# VM-MCU_v4_6.net
KiCad netlist of a schematic drawn in EAGLE
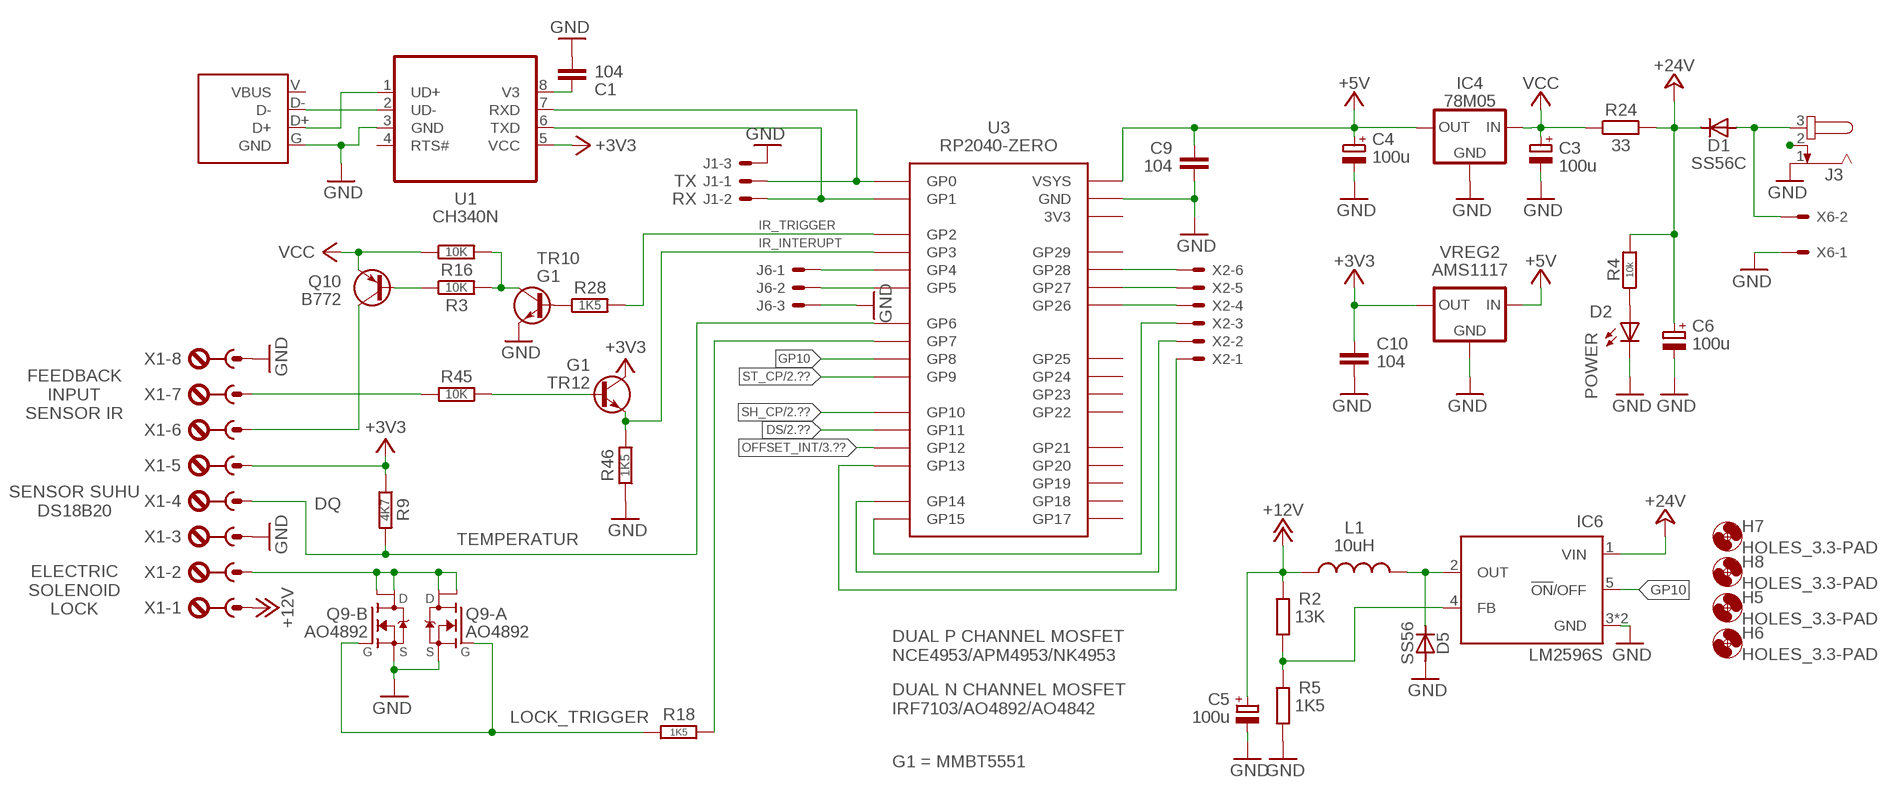
[diagram p0: schematic, sheet 1]
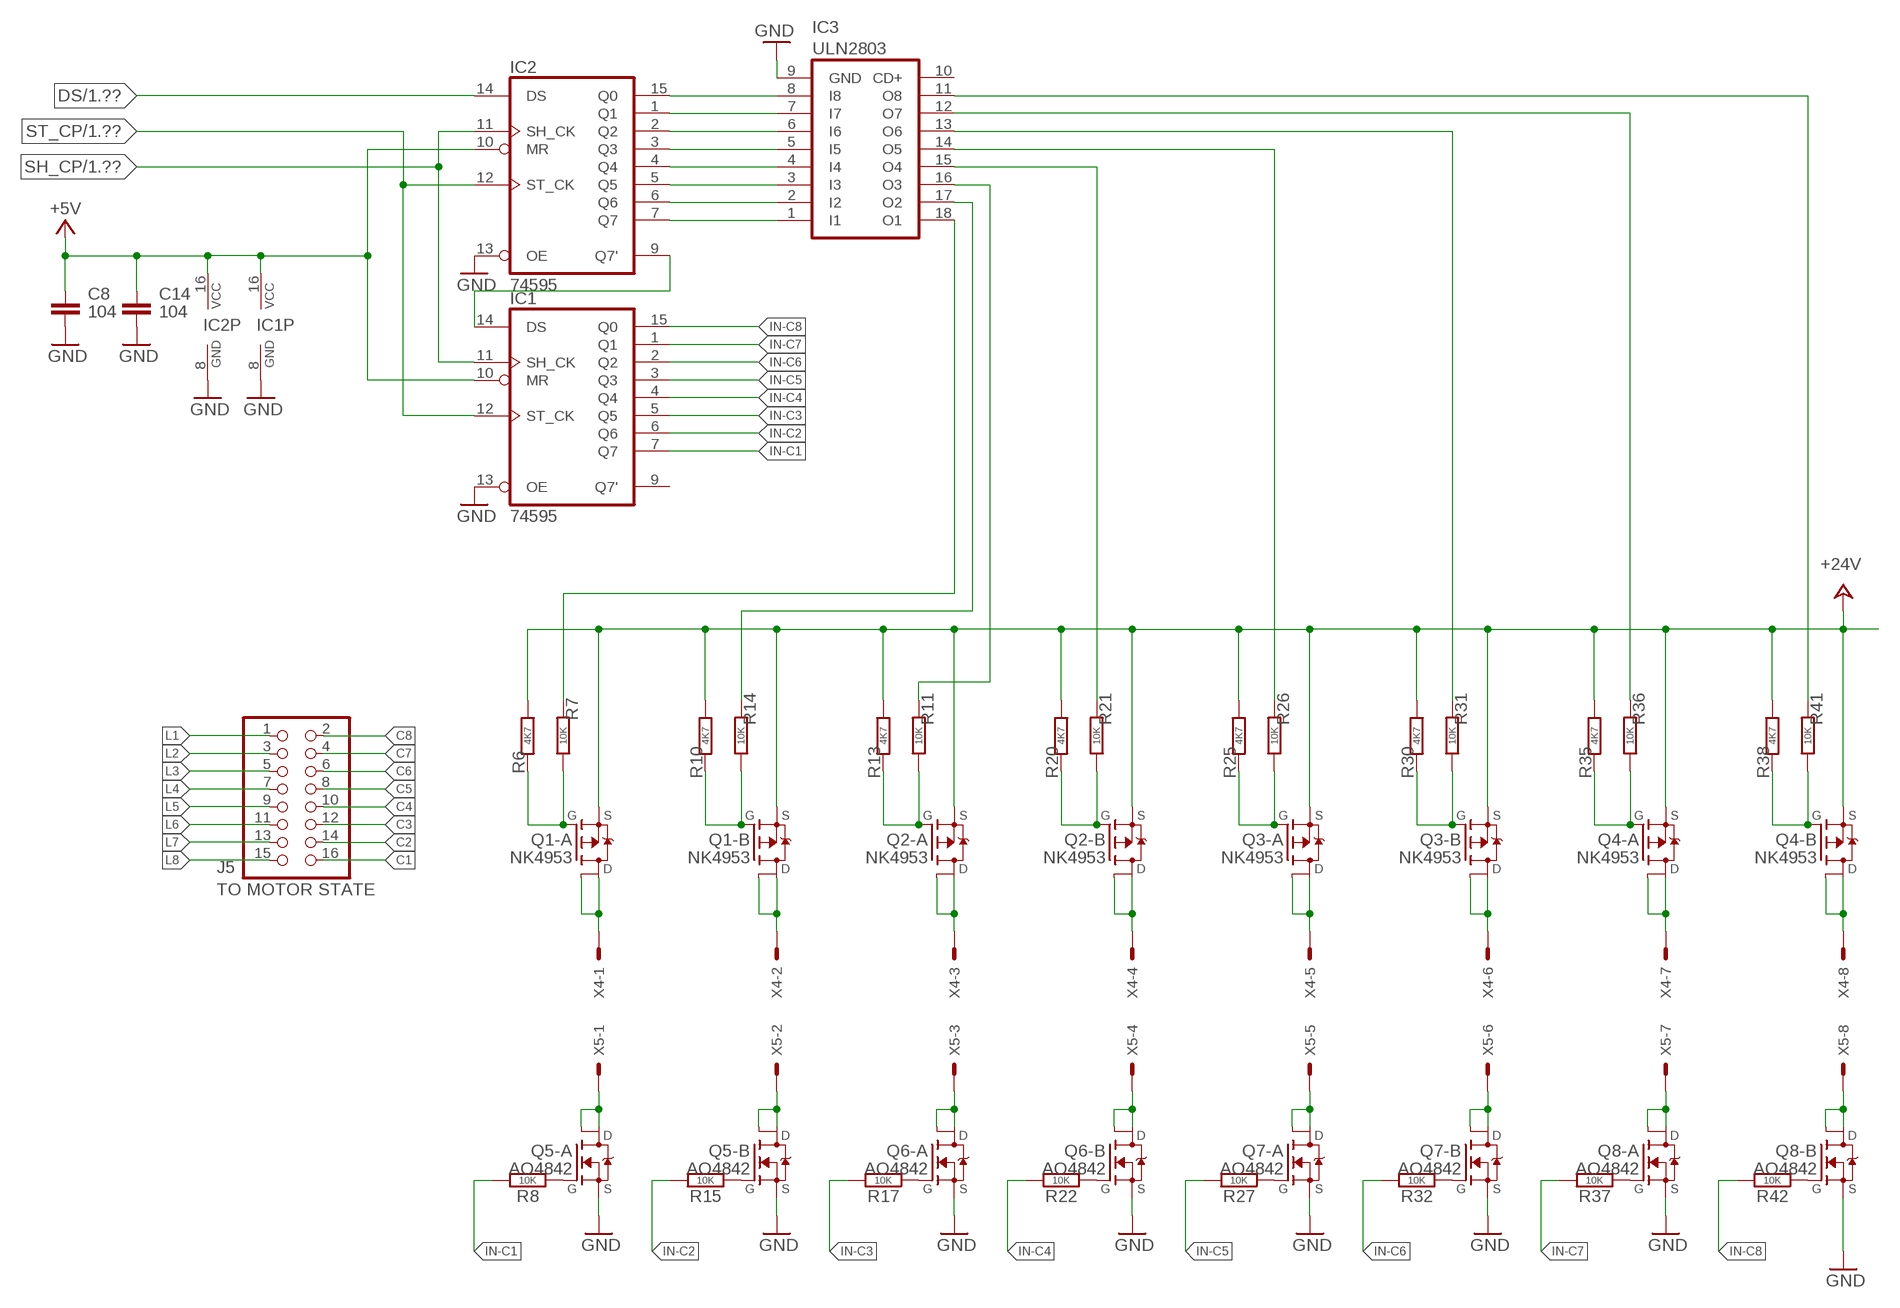
[diagram p1: schematic, sheet 2]
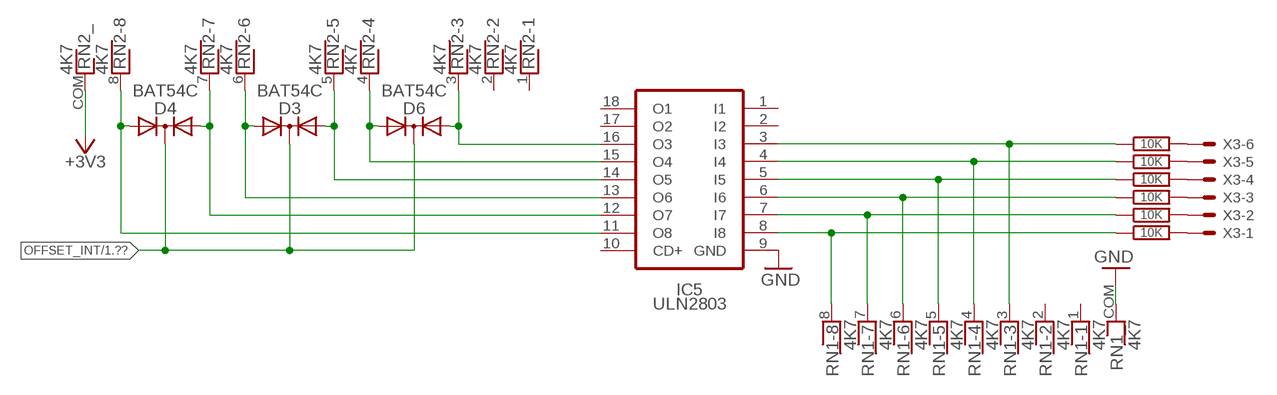
[diagram p2: schematic, sheet 3]

(export (version "E")
  (design (tool "Eeschema 10.0.6"))
  (components
    (comp (ref "C8")
      (value "104")
      (footprint "eagle-import:C1206")
      (libsource (lib "eagle-import") (part "CAP_SMD-C1206"))
    )
    (comp (ref "C14")
      (value "104")
      (footprint "eagle-import:C1206")
      (libsource (lib "eagle-import") (part "CAP_SMD-C1206"))
    )
    (comp (ref "IC1")
      (value "74595")
      (footprint "eagle-import:SO16")
      (libsource (lib "eagle-import") (part "74595"))
    )
    (comp (ref "IC2")
      (value "74595")
      (footprint "eagle-import:SO16")
      (libsource (lib "eagle-import") (part "74595"))
    )
    (comp (ref "IC3")
      (value "ULN2803")
      (footprint "eagle-import:SO18W")
      (libsource (lib "eagle-import") (part "ULN2805ASO18"))
    )
    (comp (ref "J5")
      (value "TO MOTOR STATE")
      (footprint "eagle-import:PINHEAD-SMT_2X08")
      (libsource (lib "eagle-import") (part "PINHEAD_2X8SMT"))
    )
    (comp (ref "Q1")
      (value "NK4953")
      (footprint "eagle-import:SO-8")
      (libsource (lib "eagle-import") (part "DUALFET-P_P+PNCE4953"))
    )
    (comp (ref "Q2")
      (value "NK4953")
      (footprint "eagle-import:SO-8")
      (libsource (lib "eagle-import") (part "DUALFET-P_P+PNCE4953"))
    )
    (comp (ref "Q3")
      (value "NK4953")
      (footprint "eagle-import:SO-8")
      (libsource (lib "eagle-import") (part "DUALFET-P_P+PNCE4953"))
    )
    (comp (ref "Q4")
      (value "NK4953")
      (footprint "eagle-import:SO-8")
      (libsource (lib "eagle-import") (part "DUALFET-P_P+PNCE4953"))
    )
    (comp (ref "Q5")
      (value "AO4842")
      (footprint "eagle-import:SO-8")
      (libsource (lib "eagle-import") (part "DUALFET-N_N+NAO4892"))
    )
    (comp (ref "Q6")
      (value "AO4842")
      (footprint "eagle-import:SO-8")
      (libsource (lib "eagle-import") (part "DUALFET-N_N+NAO4892"))
    )
    (comp (ref "Q7")
      (value "AO4842")
      (footprint "eagle-import:SO-8")
      (libsource (lib "eagle-import") (part "DUALFET-N_N+NAO4892"))
    )
    (comp (ref "Q8")
      (value "AO4842")
      (footprint "eagle-import:SO-8")
      (libsource (lib "eagle-import") (part "DUALFET-N_N+NAO4892"))
    )
    (comp (ref "R6")
      (value "4K7")
      (footprint "eagle-import:R1206")
      (libsource (lib "eagle-import") (part "RESISTOR_1206"))
    )
    (comp (ref "R7")
      (value "10K")
      (footprint "eagle-import:R1206")
      (libsource (lib "eagle-import") (part "RESISTOR_1206"))
    )
    (comp (ref "R8")
      (value "10K")
      (footprint "eagle-import:R1206")
      (libsource (lib "eagle-import") (part "RESISTOR_1206"))
    )
    (comp (ref "R10")
      (value "4K7")
      (footprint "eagle-import:R1206")
      (libsource (lib "eagle-import") (part "RESISTOR_1206"))
    )
    (comp (ref "R11")
      (value "10K")
      (footprint "eagle-import:R1206")
      (libsource (lib "eagle-import") (part "RESISTOR_1206"))
    )
    (comp (ref "R13")
      (value "4K7")
      (footprint "eagle-import:R1206")
      (libsource (lib "eagle-import") (part "RESISTOR_1206"))
    )
    (comp (ref "R14")
      (value "10K")
      (footprint "eagle-import:R1206")
      (libsource (lib "eagle-import") (part "RESISTOR_1206"))
    )
    (comp (ref "R15")
      (value "10K")
      (footprint "eagle-import:R1206")
      (libsource (lib "eagle-import") (part "RESISTOR_1206"))
    )
    (comp (ref "R17")
      (value "10K")
      (footprint "eagle-import:R1206")
      (libsource (lib "eagle-import") (part "RESISTOR_1206"))
    )
    (comp (ref "R20")
      (value "4K7")
      (footprint "eagle-import:R1206")
      (libsource (lib "eagle-import") (part "RESISTOR_1206"))
    )
    (comp (ref "R21")
      (value "10K")
      (footprint "eagle-import:R1206")
      (libsource (lib "eagle-import") (part "RESISTOR_1206"))
    )
    (comp (ref "R22")
      (value "10K")
      (footprint "eagle-import:R1206")
      (libsource (lib "eagle-import") (part "RESISTOR_1206"))
    )
    (comp (ref "R25")
      (value "4K7")
      (footprint "eagle-import:R1206")
      (libsource (lib "eagle-import") (part "RESISTOR_1206"))
    )
    (comp (ref "R26")
      (value "10K")
      (footprint "eagle-import:R1206")
      (libsource (lib "eagle-import") (part "RESISTOR_1206"))
    )
    (comp (ref "R27")
      (value "10K")
      (footprint "eagle-import:R1206")
      (libsource (lib "eagle-import") (part "RESISTOR_1206"))
    )
    (comp (ref "R30")
      (value "4K7")
      (footprint "eagle-import:R1206")
      (libsource (lib "eagle-import") (part "RESISTOR_1206"))
    )
    (comp (ref "R31")
      (value "10K")
      (footprint "eagle-import:R1206")
      (libsource (lib "eagle-import") (part "RESISTOR_1206"))
    )
    (comp (ref "R32")
      (value "10K")
      (footprint "eagle-import:R1206")
      (libsource (lib "eagle-import") (part "RESISTOR_1206"))
    )
    (comp (ref "R35")
      (value "4K7")
      (footprint "eagle-import:R1206")
      (libsource (lib "eagle-import") (part "RESISTOR_1206"))
    )
    (comp (ref "R36")
      (value "10K")
      (footprint "eagle-import:R1206")
      (libsource (lib "eagle-import") (part "RESISTOR_1206"))
    )
    (comp (ref "R37")
      (value "10K")
      (footprint "eagle-import:R1206")
      (libsource (lib "eagle-import") (part "RESISTOR_1206"))
    )
    (comp (ref "R38")
      (value "4K7")
      (footprint "eagle-import:R1206")
      (libsource (lib "eagle-import") (part "RESISTOR_1206"))
    )
    (comp (ref "R41")
      (value "10K")
      (footprint "eagle-import:R1206")
      (libsource (lib "eagle-import") (part "RESISTOR_1206"))
    )
    (comp (ref "R42")
      (value "10K")
      (footprint "eagle-import:R1206")
      (libsource (lib "eagle-import") (part "RESISTOR_1206"))
    )
    (comp (ref "X4")
      (value "SOKET-8P_MOLEX-3.96")
      (footprint "eagle-import:8P-MOLEX")
      (fields (field (name "MF") "MOLEX"))
      (libsource (lib "eagle-import") (part "SOKET-8P_MOLEX-3.96"))
    )
    (comp (ref "X5")
      (value "SOKET-8P_MOLEX-3.96")
      (footprint "eagle-import:8P-MOLEX")
      (fields (field (name "MF") "MOLEX"))
      (libsource (lib "eagle-import") (part "SOKET-8P_MOLEX-3.96"))
    )
    (comp (ref "C1")
      (value "104")
      (footprint "eagle-import:C1206")
      (libsource (lib "eagle-import") (part "CAP_SMD-C1206"))
    )
    (comp (ref "C3")
      (value "100u")
      (footprint "eagle-import:UD-6,3X7,7_NICHICON")
      (libsource (lib "eagle-import") (part "ELCO_UD-6,3X7,7"))
    )
    (comp (ref "C4")
      (value "100u")
      (footprint "eagle-import:UD-6,3X7,7_NICHICON")
      (libsource (lib "eagle-import") (part "ELCO_UD-6,3X7,7"))
    )
    (comp (ref "C5")
      (value "100u")
      (footprint "eagle-import:UD-6,3X7,7_NICHICON")
      (libsource (lib "eagle-import") (part "ELCO_UD-6,3X7,7"))
    )
    (comp (ref "C6")
      (value "100u")
      (footprint "eagle-import:UD-6,3X7,7_NICHICON")
      (libsource (lib "eagle-import") (part "ELCO_UD-6,3X7,7"))
    )
    (comp (ref "C9")
      (value "104")
      (footprint "eagle-import:C1206")
      (libsource (lib "eagle-import") (part "CAP_SMD-C1206"))
    )
    (comp (ref "C10")
      (value "104")
      (footprint "eagle-import:C1206")
      (libsource (lib "eagle-import") (part "CAP_SMD-C1206"))
    )
    (comp (ref "D1")
      (value "SS56C")
      (footprint "eagle-import:DO214AB")
      (libsource (lib "eagle-import") (part "DIODE_DO214AB-SMC"))
    )
    (comp (ref "D2")
      (value "POWER")
      (footprint "eagle-import:LED2835")
      (libsource (lib "eagle-import") (part "LED2835"))
    )
    (comp (ref "D5")
      (value "SS56")
      (footprint "eagle-import:DO214AC")
      (libsource (lib "eagle-import") (part "DIODE_DO214AC"))
    )
    (comp (ref "H5")
      (value "HOLES_3.3-PAD")
      (footprint "eagle-import:3,3-PAD")
      (libsource (lib "eagle-import") (part "HOLES_3.3-PAD"))
    )
    (comp (ref "H6")
      (value "HOLES_3.3-PAD")
      (footprint "eagle-import:3,3-PAD")
      (libsource (lib "eagle-import") (part "HOLES_3.3-PAD"))
    )
    (comp (ref "H7")
      (value "HOLES_3.3-PAD")
      (footprint "eagle-import:3,3-PAD")
      (libsource (lib "eagle-import") (part "HOLES_3.3-PAD"))
    )
    (comp (ref "H8")
      (value "HOLES_3.3-PAD")
      (footprint "eagle-import:3,3-PAD")
      (libsource (lib "eagle-import") (part "HOLES_3.3-PAD"))
    )
    (comp (ref "IC4")
      (value "78M05")
      (footprint "eagle-import:TO252")
      (libsource (lib "eagle-import") (part "78XXX_TO252"))
    )
    (comp (ref "IC6")
      (value "LM2596S")
      (footprint "eagle-import:TO263-5")
      (fields (field (name "MF") "NATIONAL SEMICONDUCTOR") (field (name "MPN") "LM2596S-ADJ/NOPB"))
      (libsource (lib "eagle-import") (part "LM2596S"))
    )
    (comp (ref "J1")
      (value "SOKET-3P_JST-XH-2.54")
      (footprint "eagle-import:3P-JST-XH")
      (libsource (lib "eagle-import") (part "SOKET-3P_JST-XH-2.54"))
    )
    (comp (ref "J3")
      (value "JACK-DC_5.5X2.1MM")
      (footprint "eagle-import:DC-5.5X2.1")
      (libsource (lib "eagle-import") (part "JACK-DC_5.5X2.1MM"))
    )
    (comp (ref "J6")
      (value "SOKET-3P_JST-XH-2.54")
      (footprint "eagle-import:3P-JST-XH")
      (libsource (lib "eagle-import") (part "SOKET-3P_JST-XH-2.54"))
    )
    (comp (ref "L1")
      (value "10uH")
      (footprint "eagle-import:CDRH127_LD")
      (libsource (lib "eagle-import") (part "INDUKTORSMD"))
    )
    (comp (ref "Q9")
      (value "AO4892")
      (footprint "eagle-import:SO-8")
      (libsource (lib "eagle-import") (part "DUALFET-N_N+NAO4892"))
    )
    (comp (ref "Q10")
      (value "B772")
      (footprint "eagle-import:SOT89-BCE")
      (libsource (lib "eagle-import") (part "BJT-PNP_SOT89"))
    )
    (comp (ref "R2")
      (value "13K")
      (footprint "eagle-import:R1206")
      (libsource (lib "eagle-import") (part "VM-MCU_RESISTOR_1206"))
    )
    (comp (ref "R3")
      (value "10K")
      (footprint "eagle-import:R1206")
      (libsource (lib "eagle-import") (part "VM-MCU_RESISTOR_1206"))
    )
    (comp (ref "R4")
      (value "10k")
      (footprint "eagle-import:R1206")
      (libsource (lib "eagle-import") (part "RESISTOR_1206"))
    )
    (comp (ref "R5")
      (value "1K5")
      (footprint "eagle-import:R1206")
      (libsource (lib "eagle-import") (part "VM-MCU_RESISTOR_1206"))
    )
    (comp (ref "R9")
      (value "4K7")
      (footprint "eagle-import:R1206")
      (libsource (lib "eagle-import") (part "VM-MCU_RESISTOR_1206"))
    )
    (comp (ref "R16")
      (value "10K")
      (footprint "eagle-import:R1206")
      (libsource (lib "eagle-import") (part "VM-MCU_RESISTOR_1206"))
    )
    (comp (ref "R18")
      (value "1K5")
      (footprint "eagle-import:R1206")
      (libsource (lib "eagle-import") (part "VM-MCU_RESISTOR_1206"))
    )
    (comp (ref "R24")
      (value "33")
      (footprint "eagle-import:2W-15")
      (libsource (lib "eagle-import") (part "RESISTOR_0615/15"))
    )
    (comp (ref "R28")
      (value "1K5")
      (footprint "eagle-import:R1206")
      (libsource (lib "eagle-import") (part "VM-MCU_RESISTOR_1206"))
    )
    (comp (ref "R45")
      (value "10K")
      (footprint "eagle-import:R1206")
      (libsource (lib "eagle-import") (part "RESISTOR_1206"))
    )
    (comp (ref "R46")
      (value "1K5")
      (footprint "eagle-import:R1206")
      (libsource (lib "eagle-import") (part "VM-MCU_RESISTOR_1206"))
    )
    (comp (ref "TR10")
      (value "G1")
      (footprint "eagle-import:SOT23-BEC")
      (libsource (lib "eagle-import") (part "BJT-NPN_SOT23-BEC"))
    )
    (comp (ref "TR12")
      (value "G1")
      (footprint "eagle-import:SOT23-BEC")
      (libsource (lib "eagle-import") (part "BJT-NPN_SOT23-BEC"))
    )
    (comp (ref "U$3")
      (value "USB-C_BREAKOUT_")
      (footprint "eagle-import:USB-C_4P")
      (libsource (lib "eagle-import") (part "USB-C_BREAKOUT_"))
    )
    (comp (ref "U1")
      (value "CH340N")
      (footprint "eagle-import:SO-8")
      (libsource (lib "eagle-import") (part "CH340N"))
    )
    (comp (ref "U3")
      (value "RP2040-ZERO")
      (footprint "eagle-import:PICO-ZERO")
      (libsource (lib "eagle-import") (part "RASPBERRY-PICO-ZERO_"))
    )
    (comp (ref "VREG2")
      (value "AMS1117")
      (footprint "eagle-import:SOT223")
      (libsource (lib "eagle-import") (part "78XXX_SOT223"))
    )
    (comp (ref "X1")
      (value "TBLOCK-8P_KF2EDG-3.81")
      (footprint "eagle-import:KF2EDG-3.81_8P")
      (libsource (lib "eagle-import") (part "TBLOCK-8P_KF2EDG-3.81"))
    )
    (comp (ref "X2")
      (value "SOKET-6P_JST-XH-2.54")
      (footprint "eagle-import:6P-JST-XH")
      (libsource (lib "eagle-import") (part "SOKET-6P_JST-XH-2.54"))
    )
    (comp (ref "X6")
      (value "SOKET-2P_MOLEX-3.96")
      (footprint "eagle-import:2P-MOLEX")
      (fields (field (name "MF") "MOLEX"))
      (libsource (lib "eagle-import") (part "SOKET-2P_MOLEX-3.96"))
    )
    (comp (ref "D3")
      (value "BAT54C")
      (footprint "eagle-import:SOT23-BCE")
      (libsource (lib "eagle-import") (part "DIODE-3PIN_COMMON-CATHODE"))
    )
    (comp (ref "D4")
      (value "BAT54C")
      (footprint "eagle-import:SOT23-BCE")
      (libsource (lib "eagle-import") (part "DIODE-3PIN_COMMON-CATHODE"))
    )
    (comp (ref "D6")
      (value "BAT54C")
      (footprint "eagle-import:SOT23-BCE")
      (libsource (lib "eagle-import") (part "DIODE-3PIN_COMMON-CATHODE"))
    )
    (comp (ref "IC5")
      (value "ULN2803")
      (footprint "eagle-import:SO18W")
      (libsource (lib "eagle-import") (part "ULN2805ASO18"))
    )
    (comp (ref "R39")
      (value "10K")
      (footprint "eagle-import:R1206")
      (libsource (lib "eagle-import") (part "VM-MCU_RESISTOR_1206"))
    )
    (comp (ref "R43")
      (value "10K")
      (footprint "eagle-import:R1206")
      (libsource (lib "eagle-import") (part "VM-MCU_RESISTOR_1206"))
    )
    (comp (ref "R44")
      (value "10K")
      (footprint "eagle-import:R1206")
      (libsource (lib "eagle-import") (part "VM-MCU_RESISTOR_1206"))
    )
    (comp (ref "R47")
      (value "10K")
      (footprint "eagle-import:R1206")
      (libsource (lib "eagle-import") (part "VM-MCU_RESISTOR_1206"))
    )
    (comp (ref "R48")
      (value "10K")
      (footprint "eagle-import:R1206")
      (libsource (lib "eagle-import") (part "VM-MCU_RESISTOR_1206"))
    )
    (comp (ref "R49")
      (value "10K")
      (footprint "eagle-import:R1206")
      (libsource (lib "eagle-import") (part "VM-MCU_RESISTOR_1206"))
    )
    (comp (ref "RN1")
      (value "4K7")
      (footprint "eagle-import:RN-9")
      (libsource (lib "eagle-import") (part "RESISTOR-PACK-X8_"))
    )
    (comp (ref "RN2")
      (value "4K7")
      (footprint "eagle-import:RN-9")
      (libsource (lib "eagle-import") (part "RESISTOR-PACK-X8_"))
    )
    (comp (ref "X3")
      (value "SOKET-6P_MOLEX-3.96")
      (footprint "eagle-import:6P-MOLEX")
      (fields (field (name "MF") "MOLEX"))
      (libsource (lib "eagle-import") (part "SOKET-6P_MOLEX-3.96"))
    )
  )
  (nets
    (net (code "1") (name "+3V3") (class "Default")
      (node (ref "C10") (pin "1") (pinfunction "1_1") (pintype "passive"))
      (node (ref "R9") (pin "1") (pinfunction "1_1") (pintype "passive"))
      (node (ref "RN2") (pin "COM") (pinfunction "1_COM") (pintype "passive"))
      (node (ref "TR12") (pin "C") (pinfunction "C_C") (pintype "passive"))
      (node (ref "U1") (pin "5") (pinfunction "VCC_5") (pintype "power_in"))
      (node (ref "VREG2") (pin "4") (pinfunction "OUT_4") (pintype "passive"))
      (node (ref "X1") (pin "5") (pinfunction "1_5") (pintype "passive"))
    )
    (net (code "2") (name "+5V") (class "Default")
      (node (ref "C14") (pin "1") (pinfunction "1_1") (pintype "passive"))
      (node (ref "C4") (pin "+") (pinfunction "+_+") (pintype "passive"))
      (node (ref "C8") (pin "1") (pinfunction "1_1") (pintype "passive"))
      (node (ref "C9") (pin "1") (pinfunction "1_1") (pintype "passive"))
      (node (ref "IC1") (pin "10") (pinfunction "MR_10") (pintype "input"))
      (node (ref "IC1") (pin "16") (pinfunction "VCC_16") (pintype "power_in"))
      (node (ref "IC2") (pin "10") (pinfunction "MR_10") (pintype "input"))
      (node (ref "IC2") (pin "16") (pinfunction "VCC_16") (pintype "power_in"))
      (node (ref "IC4") (pin "2") (pinfunction "OUT_2") (pintype "passive"))
      (node (ref "U3") (pin "5V") (pinfunction "VSYS_5V") (pintype "power_in"))
      (node (ref "VREG2") (pin "3") (pinfunction "IN_3") (pintype "input"))
    )
    (net (code "3") (name "+12V") (class "Default")
      (node (ref "C5") (pin "+") (pinfunction "+_+") (pintype "passive"))
      (node (ref "L1") (pin "1") (pinfunction "1_1") (pintype "passive"))
      (node (ref "R2") (pin "1") (pinfunction "1_1") (pintype "passive"))
      (node (ref "X1") (pin "1") (pinfunction "1_1") (pintype "passive"))
    )
    (net (code "4") (name "+24V") (class "Default")
      (node (ref "C6") (pin "+") (pinfunction "+_+") (pintype "passive"))
      (node (ref "D1") (pin "C") (pinfunction "C_C") (pintype "passive"))
      (node (ref "IC6") (pin "1") (pinfunction "VIN_1") (pintype "input"))
      (node (ref "Q1") (pin "1") (pinfunction "S_1") (pintype "passive"))
      (node (ref "Q1") (pin "3") (pinfunction "S_3") (pintype "passive"))
      (node (ref "Q2") (pin "1") (pinfunction "S_1") (pintype "passive"))
      (node (ref "Q2") (pin "3") (pinfunction "S_3") (pintype "passive"))
      (node (ref "Q3") (pin "1") (pinfunction "S_1") (pintype "passive"))
      (node (ref "Q3") (pin "3") (pinfunction "S_3") (pintype "passive"))
      (node (ref "Q4") (pin "1") (pinfunction "S_1") (pintype "passive"))
      (node (ref "Q4") (pin "3") (pinfunction "S_3") (pintype "passive"))
      (node (ref "R10") (pin "1") (pinfunction "1_1") (pintype "passive"))
      (node (ref "R13") (pin "1") (pinfunction "1_1") (pintype "passive"))
      (node (ref "R20") (pin "1") (pinfunction "1_1") (pintype "passive"))
      (node (ref "R24") (pin "2") (pinfunction "2_2") (pintype "passive"))
      (node (ref "R25") (pin "1") (pinfunction "1_1") (pintype "passive"))
      (node (ref "R30") (pin "1") (pinfunction "1_1") (pintype "passive"))
      (node (ref "R35") (pin "1") (pinfunction "1_1") (pintype "passive"))
      (node (ref "R38") (pin "1") (pinfunction "1_1") (pintype "passive"))
      (node (ref "R4") (pin "2") (pinfunction "2_2") (pintype "passive"))
      (node (ref "R6") (pin "1") (pinfunction "1_1") (pintype "passive"))
    )
    (net (code "5") (name "3V3") (class "Default")
      (node (ref "U3") (pin "3V3") (pinfunction "3V3_3V3") (pintype "power_in"))
    )
    (net (code "6") (name "C1") (class "Default")
      (node (ref "J5") (pin "16") (pinfunction "16_16") (pintype "passive"))
      (node (ref "Q5") (pin "7") (pinfunction "D2_7") (pintype "passive"))
      (node (ref "Q5") (pin "8") (pinfunction "D1_8") (pintype "passive"))
      (node (ref "X5") (pin "1") (pinfunction "S_1") (pintype "passive"))
    )
    (net (code "7") (name "C2") (class "Default")
      (node (ref "J5") (pin "14") (pinfunction "14_14") (pintype "passive"))
      (node (ref "Q5") (pin "5") (pinfunction "D1_5") (pintype "passive"))
      (node (ref "Q5") (pin "6") (pinfunction "D2_6") (pintype "passive"))
      (node (ref "X5") (pin "2") (pinfunction "S_2") (pintype "passive"))
    )
    (net (code "8") (name "C3") (class "Default")
      (node (ref "J5") (pin "12") (pinfunction "12_12") (pintype "passive"))
      (node (ref "Q6") (pin "7") (pinfunction "D2_7") (pintype "passive"))
      (node (ref "Q6") (pin "8") (pinfunction "D1_8") (pintype "passive"))
      (node (ref "X5") (pin "3") (pinfunction "S_3") (pintype "passive"))
    )
    (net (code "9") (name "C4") (class "Default")
      (node (ref "J5") (pin "10") (pinfunction "10_10") (pintype "passive"))
      (node (ref "Q6") (pin "5") (pinfunction "D1_5") (pintype "passive"))
      (node (ref "Q6") (pin "6") (pinfunction "D2_6") (pintype "passive"))
      (node (ref "X5") (pin "4") (pinfunction "S_4") (pintype "passive"))
    )
    (net (code "10") (name "C5") (class "Default")
      (node (ref "J5") (pin "8") (pinfunction "8_8") (pintype "passive"))
      (node (ref "Q7") (pin "7") (pinfunction "D2_7") (pintype "passive"))
      (node (ref "Q7") (pin "8") (pinfunction "D1_8") (pintype "passive"))
      (node (ref "X5") (pin "5") (pinfunction "S_5") (pintype "passive"))
    )
    (net (code "11") (name "C6") (class "Default")
      (node (ref "J5") (pin "6") (pinfunction "6_6") (pintype "passive"))
      (node (ref "Q7") (pin "5") (pinfunction "D1_5") (pintype "passive"))
      (node (ref "Q7") (pin "6") (pinfunction "D2_6") (pintype "passive"))
      (node (ref "X5") (pin "6") (pinfunction "S_6") (pintype "passive"))
    )
    (net (code "12") (name "C7") (class "Default")
      (node (ref "J5") (pin "4") (pinfunction "4_4") (pintype "passive"))
      (node (ref "Q8") (pin "7") (pinfunction "D2_7") (pintype "passive"))
      (node (ref "Q8") (pin "8") (pinfunction "D1_8") (pintype "passive"))
      (node (ref "X5") (pin "7") (pinfunction "S_7") (pintype "passive"))
    )
    (net (code "13") (name "C8") (class "Default")
      (node (ref "J5") (pin "2") (pinfunction "2_2") (pintype "passive"))
      (node (ref "Q8") (pin "5") (pinfunction "D1_5") (pintype "passive"))
      (node (ref "Q8") (pin "6") (pinfunction "D2_6") (pintype "passive"))
      (node (ref "X5") (pin "8") (pinfunction "S_8") (pintype "passive"))
    )
    (net (code "14") (name "DS") (class "Default")
      (node (ref "IC2") (pin "14") (pinfunction "DS_14") (pintype "input"))
      (node (ref "U3") (pin "P11") (pinfunction "GP11_P11") (pintype "bidirectional"))
    )
    (net (code "15") (name "GND") (class "Default")
      (node (ref "C1") (pin "2") (pinfunction "2_2") (pintype "passive"))
      (node (ref "C10") (pin "2") (pinfunction "2_2") (pintype "passive"))
      (node (ref "C14") (pin "2") (pinfunction "2_2") (pintype "passive"))
      (node (ref "C3") (pin "-") (pinfunction "-_-") (pintype "passive"))
      (node (ref "C4") (pin "-") (pinfunction "-_-") (pintype "passive"))
      (node (ref "C5") (pin "-") (pinfunction "-_-") (pintype "passive"))
      (node (ref "C6") (pin "-") (pinfunction "-_-") (pintype "passive"))
      (node (ref "C8") (pin "2") (pinfunction "2_2") (pintype "passive"))
      (node (ref "C9") (pin "2") (pinfunction "2_2") (pintype "passive"))
      (node (ref "D2") (pin "C") (pinfunction "C_C") (pintype "passive"))
      (node (ref "D5") (pin "A") (pinfunction "A_A") (pintype "passive"))
      (node (ref "IC1") (pin "13") (pinfunction "OE_13") (pintype "input"))
      (node (ref "IC1") (pin "8") (pinfunction "GND_8") (pintype "power_in"))
      (node (ref "IC2") (pin "13") (pinfunction "OE_13") (pintype "input"))
      (node (ref "IC2") (pin "8") (pinfunction "GND_8") (pintype "power_in"))
      (node (ref "IC3") (pin "9") (pinfunction "GND_9") (pintype "power_in"))
      (node (ref "IC4") (pin "3") (pinfunction "GND_3") (pintype "input"))
      (node (ref "IC5") (pin "9") (pinfunction "GND_9") (pintype "power_in"))
      (node (ref "IC6") (pin "3") (pinfunction "GND_3") (pintype "power_in"))
      (node (ref "IC6") (pin "6") (pinfunction "GND_6") (pintype "power_in"))
      (node (ref "J1") (pin "3") (pinfunction "S_3") (pintype "passive"))
      (node (ref "J3") (pin "1") (pinfunction "1_1") (pintype "passive"))
      (node (ref "J6") (pin "3") (pinfunction "S_3") (pintype "passive"))
      (node (ref "Q5") (pin "1") (pinfunction "S_1") (pintype "passive"))
      (node (ref "Q5") (pin "3") (pinfunction "S_3") (pintype "passive"))
      (node (ref "Q6") (pin "1") (pinfunction "S_1") (pintype "passive"))
      (node (ref "Q6") (pin "3") (pinfunction "S_3") (pintype "passive"))
      (node (ref "Q7") (pin "1") (pinfunction "S_1") (pintype "passive"))
      (node (ref "Q7") (pin "3") (pinfunction "S_3") (pintype "passive"))
      (node (ref "Q8") (pin "1") (pinfunction "S_1") (pintype "passive"))
      (node (ref "Q8") (pin "3") (pinfunction "S_3") (pintype "passive"))
      (node (ref "Q9") (pin "1") (pinfunction "S_1") (pintype "passive"))
      (node (ref "Q9") (pin "3") (pinfunction "S_3") (pintype "passive"))
      (node (ref "R46") (pin "1") (pinfunction "1_1") (pintype "passive"))
      (node (ref "R5") (pin "2") (pinfunction "2_2") (pintype "passive"))
      (node (ref "RN1") (pin "COM") (pinfunction "1_COM") (pintype "passive"))
      (node (ref "TR10") (pin "E") (pinfunction "E_E") (pintype "passive"))
      (node (ref "U$3") (pin "G") (pinfunction "GND_G") (pintype "bidirectional"))
      (node (ref "U1") (pin "3") (pinfunction "GND_3") (pintype "power_in"))
      (node (ref "U3") (pin "G") (pinfunction "GND_G") (pintype "power_in"))
      (node (ref "VREG2") (pin "1") (pinfunction "GND_1") (pintype "input"))
      (node (ref "X1") (pin "3") (pinfunction "1_3") (pintype "passive"))
      (node (ref "X1") (pin "8") (pinfunction "1_8") (pintype "passive"))
      (node (ref "X6") (pin "1") (pinfunction "S_1") (pintype "passive"))
    )
    (net (code "16") (name "GP10") (class "Default")
      (node (ref "IC6") (pin "5") (pinfunction "~{ON}/OFF_5") (pintype "input"))
      (node (ref "U3") (pin "P8") (pinfunction "GP8_P8") (pintype "bidirectional"))
    )
    (net (code "17") (name "IN-C1") (class "Default")
      (node (ref "IC1") (pin "7") (pinfunction "Q7_7") (pintype "tri_state"))
      (node (ref "R8") (pin "2") (pinfunction "2_2") (pintype "passive"))
    )
    (net (code "18") (name "IN-C2") (class "Default")
      (node (ref "IC1") (pin "6") (pinfunction "Q6_6") (pintype "tri_state"))
      (node (ref "R15") (pin "2") (pinfunction "2_2") (pintype "passive"))
    )
    (net (code "19") (name "IN-C3") (class "Default")
      (node (ref "IC1") (pin "5") (pinfunction "Q5_5") (pintype "tri_state"))
      (node (ref "R17") (pin "2") (pinfunction "2_2") (pintype "passive"))
    )
    (net (code "20") (name "IN-C4") (class "Default")
      (node (ref "IC1") (pin "4") (pinfunction "Q4_4") (pintype "tri_state"))
      (node (ref "R22") (pin "2") (pinfunction "2_2") (pintype "passive"))
    )
    (net (code "21") (name "IN-C5") (class "Default")
      (node (ref "IC1") (pin "3") (pinfunction "Q3_3") (pintype "tri_state"))
      (node (ref "R27") (pin "2") (pinfunction "2_2") (pintype "passive"))
    )
    (net (code "22") (name "IN-C6") (class "Default")
      (node (ref "IC1") (pin "2") (pinfunction "Q2_2") (pintype "tri_state"))
      (node (ref "R32") (pin "2") (pinfunction "2_2") (pintype "passive"))
    )
    (net (code "23") (name "IN-C7") (class "Default")
      (node (ref "IC1") (pin "1") (pinfunction "Q1_1") (pintype "tri_state"))
      (node (ref "R37") (pin "2") (pinfunction "2_2") (pintype "passive"))
    )
    (net (code "24") (name "IN-C8") (class "Default")
      (node (ref "IC1") (pin "15") (pinfunction "Q0_15") (pintype "tri_state"))
      (node (ref "R42") (pin "2") (pinfunction "2_2") (pintype "passive"))
    )
    (net (code "25") (name "L1") (class "Default")
      (node (ref "J5") (pin "1") (pinfunction "1_1") (pintype "passive"))
      (node (ref "Q1") (pin "7") (pinfunction "D2_7") (pintype "passive"))
      (node (ref "Q1") (pin "8") (pinfunction "D1_8") (pintype "passive"))
      (node (ref "X4") (pin "1") (pinfunction "S_1") (pintype "passive"))
    )
    (net (code "26") (name "L2") (class "Default")
      (node (ref "J5") (pin "3") (pinfunction "3_3") (pintype "passive"))
      (node (ref "Q1") (pin "5") (pinfunction "D1_5") (pintype "passive"))
      (node (ref "Q1") (pin "6") (pinfunction "D2_6") (pintype "passive"))
      (node (ref "X4") (pin "2") (pinfunction "S_2") (pintype "passive"))
    )
    (net (code "27") (name "L3") (class "Default")
      (node (ref "J5") (pin "5") (pinfunction "5_5") (pintype "passive"))
      (node (ref "Q2") (pin "7") (pinfunction "D2_7") (pintype "passive"))
      (node (ref "Q2") (pin "8") (pinfunction "D1_8") (pintype "passive"))
      (node (ref "X4") (pin "3") (pinfunction "S_3") (pintype "passive"))
    )
    (net (code "28") (name "L4") (class "Default")
      (node (ref "J5") (pin "7") (pinfunction "7_7") (pintype "passive"))
      (node (ref "Q2") (pin "5") (pinfunction "D1_5") (pintype "passive"))
      (node (ref "Q2") (pin "6") (pinfunction "D2_6") (pintype "passive"))
      (node (ref "X4") (pin "4") (pinfunction "S_4") (pintype "passive"))
    )
    (net (code "29") (name "L5") (class "Default")
      (node (ref "J5") (pin "9") (pinfunction "9_9") (pintype "passive"))
      (node (ref "Q3") (pin "7") (pinfunction "D2_7") (pintype "passive"))
      (node (ref "Q3") (pin "8") (pinfunction "D1_8") (pintype "passive"))
      (node (ref "X4") (pin "5") (pinfunction "S_5") (pintype "passive"))
    )
    (net (code "30") (name "L6") (class "Default")
      (node (ref "J5") (pin "11") (pinfunction "11_11") (pintype "passive"))
      (node (ref "Q3") (pin "5") (pinfunction "D1_5") (pintype "passive"))
      (node (ref "Q3") (pin "6") (pinfunction "D2_6") (pintype "passive"))
      (node (ref "X4") (pin "6") (pinfunction "S_6") (pintype "passive"))
    )
    (net (code "31") (name "L7") (class "Default")
      (node (ref "J5") (pin "13") (pinfunction "13_13") (pintype "passive"))
      (node (ref "Q4") (pin "7") (pinfunction "D2_7") (pintype "passive"))
      (node (ref "Q4") (pin "8") (pinfunction "D1_8") (pintype "passive"))
      (node (ref "X4") (pin "7") (pinfunction "S_7") (pintype "passive"))
    )
    (net (code "32") (name "L8") (class "Default")
      (node (ref "J5") (pin "15") (pinfunction "15_15") (pintype "passive"))
      (node (ref "Q4") (pin "5") (pinfunction "D1_5") (pintype "passive"))
      (node (ref "Q4") (pin "6") (pinfunction "D2_6") (pintype "passive"))
      (node (ref "X4") (pin "8") (pinfunction "S_8") (pintype "passive"))
    )
    (net (code "33") (name "Net-(D2-PadA)") (class "Default")
      (node (ref "D2") (pin "A") (pinfunction "A_A") (pintype "passive"))
      (node (ref "R4") (pin "1") (pinfunction "1_1") (pintype "passive"))
    )
    (net (code "34") (name "Net-(D3-A1)") (class "Default")
      (node (ref "D3") (pin "B") (pinfunction "A1_B") (pintype "passive"))
      (node (ref "IC5") (pin "14") (pinfunction "O5_14") (pintype "open_collector"))
      (node (ref "RN2") (pin "5") (pinfunction "1_5") (pintype "passive"))
    )
    (net (code "35") (name "Net-(D3-A2)") (class "Default")
      (node (ref "D3") (pin "E") (pinfunction "A2_E") (pintype "passive"))
      (node (ref "IC5") (pin "13") (pinfunction "O6_13") (pintype "open_collector"))
      (node (ref "RN2") (pin "6") (pinfunction "1_6") (pintype "passive"))
    )
    (net (code "36") (name "Net-(D4-A1)") (class "Default")
      (node (ref "D4") (pin "B") (pinfunction "A1_B") (pintype "passive"))
      (node (ref "IC5") (pin "12") (pinfunction "O7_12") (pintype "open_collector"))
      (node (ref "RN2") (pin "7") (pinfunction "1_7") (pintype "passive"))
    )
    (net (code "37") (name "Net-(D4-A2)") (class "Default")
      (node (ref "D4") (pin "E") (pinfunction "A2_E") (pintype "passive"))
      (node (ref "IC5") (pin "11") (pinfunction "O8_11") (pintype "open_collector"))
      (node (ref "RN2") (pin "8") (pinfunction "1_8") (pintype "passive"))
    )
    (net (code "38") (name "Net-(D6-A1)") (class "Default")
      (node (ref "D6") (pin "B") (pinfunction "A1_B") (pintype "passive"))
      (node (ref "IC5") (pin "16") (pinfunction "O3_16") (pintype "open_collector"))
      (node (ref "RN2") (pin "3") (pinfunction "1_3") (pintype "passive"))
    )
    (net (code "39") (name "Net-(D6-A2)") (class "Default")
      (node (ref "D6") (pin "E") (pinfunction "A2_E") (pintype "passive"))
      (node (ref "IC5") (pin "15") (pinfunction "O4_15") (pintype "open_collector"))
      (node (ref "RN2") (pin "4") (pinfunction "1_4") (pintype "passive"))
    )
    (net (code "40") (name "Net-(IC1A-DS)") (class "Default")
      (node (ref "IC1") (pin "14") (pinfunction "DS_14") (pintype "input"))
      (node (ref "IC2") (pin "9") (pinfunction "Q7'_9") (pintype "tri_state"))
    )
    (net (code "41") (name "Net-(IC2A-Q0)") (class "Default")
      (node (ref "IC2") (pin "15") (pinfunction "Q0_15") (pintype "tri_state"))
      (node (ref "IC3") (pin "8") (pinfunction "I8_8") (pintype "input"))
    )
    (net (code "42") (name "Net-(IC2A-Q1)") (class "Default")
      (node (ref "IC2") (pin "1") (pinfunction "Q1_1") (pintype "tri_state"))
      (node (ref "IC3") (pin "7") (pinfunction "I7_7") (pintype "input"))
    )
    (net (code "43") (name "Net-(IC2A-Q2)") (class "Default")
      (node (ref "IC2") (pin "2") (pinfunction "Q2_2") (pintype "tri_state"))
      (node (ref "IC3") (pin "6") (pinfunction "I6_6") (pintype "input"))
    )
    (net (code "44") (name "Net-(IC2A-Q3)") (class "Default")
      (node (ref "IC2") (pin "3") (pinfunction "Q3_3") (pintype "tri_state"))
      (node (ref "IC3") (pin "5") (pinfunction "I5_5") (pintype "input"))
    )
    (net (code "45") (name "Net-(IC2A-Q4)") (class "Default")
      (node (ref "IC2") (pin "4") (pinfunction "Q4_4") (pintype "tri_state"))
      (node (ref "IC3") (pin "4") (pinfunction "I4_4") (pintype "input"))
    )
    (net (code "46") (name "Net-(IC2A-Q5)") (class "Default")
      (node (ref "IC2") (pin "5") (pinfunction "Q5_5") (pintype "tri_state"))
      (node (ref "IC3") (pin "3") (pinfunction "I3_3") (pintype "input"))
    )
    (net (code "47") (name "Net-(IC2A-Q6)") (class "Default")
      (node (ref "IC2") (pin "6") (pinfunction "Q6_6") (pintype "tri_state"))
      (node (ref "IC3") (pin "2") (pinfunction "I2_2") (pintype "input"))
    )
    (net (code "48") (name "Net-(IC2A-Q7)") (class "Default")
      (node (ref "IC2") (pin "7") (pinfunction "Q7_7") (pintype "tri_state"))
      (node (ref "IC3") (pin "1") (pinfunction "I1_1") (pintype "input"))
    )
    (net (code "49") (name "Net-(IC3-O1)") (class "Default")
      (node (ref "IC3") (pin "18") (pinfunction "O1_18") (pintype "open_collector"))
      (node (ref "R7") (pin "2") (pinfunction "2_2") (pintype "passive"))
    )
    (net (code "50") (name "Net-(IC3-O2)") (class "Default")
      (node (ref "IC3") (pin "17") (pinfunction "O2_17") (pintype "open_collector"))
      (node (ref "R14") (pin "2") (pinfunction "2_2") (pintype "passive"))
    )
    (net (code "51") (name "Net-(IC3-O3)") (class "Default")
      (node (ref "IC3") (pin "16") (pinfunction "O3_16") (pintype "open_collector"))
      (node (ref "R11") (pin "2") (pinfunction "2_2") (pintype "passive"))
    )
    (net (code "52") (name "Net-(IC3-O4)") (class "Default")
      (node (ref "IC3") (pin "15") (pinfunction "O4_15") (pintype "open_collector"))
      (node (ref "R21") (pin "2") (pinfunction "2_2") (pintype "passive"))
    )
    (net (code "53") (name "Net-(IC3-O5)") (class "Default")
      (node (ref "IC3") (pin "14") (pinfunction "O5_14") (pintype "open_collector"))
      (node (ref "R26") (pin "2") (pinfunction "2_2") (pintype "passive"))
    )
    (net (code "54") (name "Net-(IC3-O6)") (class "Default")
      (node (ref "IC3") (pin "13") (pinfunction "O6_13") (pintype "open_collector"))
      (node (ref "R31") (pin "2") (pinfunction "2_2") (pintype "passive"))
    )
    (net (code "55") (name "Net-(IC3-O7)") (class "Default")
      (node (ref "IC3") (pin "12") (pinfunction "O7_12") (pintype "open_collector"))
      (node (ref "R36") (pin "2") (pinfunction "2_2") (pintype "passive"))
    )
    (net (code "56") (name "Net-(IC3-O8)") (class "Default")
      (node (ref "IC3") (pin "11") (pinfunction "O8_11") (pintype "open_collector"))
      (node (ref "R41") (pin "2") (pinfunction "2_2") (pintype "passive"))
    )
    (net (code "57") (name "Net-(IC5-I3)") (class "Default")
      (node (ref "IC5") (pin "3") (pinfunction "I3_3") (pintype "input"))
      (node (ref "R39") (pin "1") (pinfunction "1_1") (pintype "passive"))
      (node (ref "RN1") (pin "3") (pinfunction "1_3") (pintype "passive"))
    )
    (net (code "58") (name "Net-(IC5-I4)") (class "Default")
      (node (ref "IC5") (pin "4") (pinfunction "I4_4") (pintype "input"))
      (node (ref "R43") (pin "1") (pinfunction "1_1") (pintype "passive"))
      (node (ref "RN1") (pin "4") (pinfunction "1_4") (pintype "passive"))
    )
    (net (code "59") (name "Net-(IC5-I5)") (class "Default")
      (node (ref "IC5") (pin "5") (pinfunction "I5_5") (pintype "input"))
      (node (ref "R44") (pin "1") (pinfunction "1_1") (pintype "passive"))
      (node (ref "RN1") (pin "5") (pinfunction "1_5") (pintype "passive"))
    )
    (net (code "60") (name "Net-(IC5-I6)") (class "Default")
      (node (ref "IC5") (pin "6") (pinfunction "I6_6") (pintype "input"))
      (node (ref "R47") (pin "1") (pinfunction "1_1") (pintype "passive"))
      (node (ref "RN1") (pin "6") (pinfunction "1_6") (pintype "passive"))
    )
    (net (code "61") (name "Net-(IC5-I7)") (class "Default")
      (node (ref "IC5") (pin "7") (pinfunction "I7_7") (pintype "input"))
      (node (ref "R48") (pin "1") (pinfunction "1_1") (pintype "passive"))
      (node (ref "RN1") (pin "7") (pinfunction "1_7") (pintype "passive"))
    )
    (net (code "62") (name "Net-(IC5-I8)") (class "Default")
      (node (ref "IC5") (pin "8") (pinfunction "I8_8") (pintype "input"))
      (node (ref "R49") (pin "1") (pinfunction "1_1") (pintype "passive"))
      (node (ref "RN1") (pin "8") (pinfunction "1_8") (pintype "passive"))
    )
    (net (code "63") (name "Net-(IC6-FB)") (class "Default")
      (node (ref "IC6") (pin "4") (pinfunction "FB_4") (pintype "input"))
      (node (ref "R2") (pin "2") (pinfunction "2_2") (pintype "passive"))
      (node (ref "R5") (pin "1") (pinfunction "1_1") (pintype "passive"))
    )
    (net (code "64") (name "Net-(IC6-OUT)") (class "Default")
      (node (ref "D5") (pin "C") (pinfunction "C_C") (pintype "passive"))
      (node (ref "IC6") (pin "2") (pinfunction "OUT_2") (pintype "output"))
      (node (ref "L1") (pin "2") (pinfunction "2_2") (pintype "passive"))
    )
    (net (code "65") (name "Net-(J1A-S)") (class "Default")
      (node (ref "J1") (pin "1") (pinfunction "S_1") (pintype "passive"))
      (node (ref "U1") (pin "7") (pinfunction "RXD_7") (pintype "bidirectional"))
      (node (ref "U3") (pin "P0") (pinfunction "GP0_P0") (pintype "bidirectional"))
    )
    (net (code "66") (name "Net-(J1B-S)") (class "Default")
      (node (ref "J1") (pin "2") (pinfunction "S_2") (pintype "passive"))
      (node (ref "U1") (pin "6") (pinfunction "TXD_6") (pintype "bidirectional"))
      (node (ref "U3") (pin "P1") (pinfunction "GP1_P1") (pintype "bidirectional"))
    )
    (net (code "67") (name "Net-(J6A-S)") (class "Default")
      (node (ref "J6") (pin "1") (pinfunction "S_1") (pintype "passive"))
      (node (ref "U3") (pin "P4") (pinfunction "GP4_P4") (pintype "bidirectional"))
    )
    (net (code "68") (name "Net-(J6B-S)") (class "Default")
      (node (ref "J6") (pin "2") (pinfunction "S_2") (pintype "passive"))
      (node (ref "U3") (pin "P5") (pinfunction "GP5_P5") (pintype "bidirectional"))
    )
    (net (code "69") (name "Net-(Q1A-G)") (class "Default")
      (node (ref "Q1") (pin "2") (pinfunction "G_2") (pintype "passive"))
      (node (ref "R6") (pin "2") (pinfunction "2_2") (pintype "passive"))
      (node (ref "R7") (pin "1") (pinfunction "1_1") (pintype "passive"))
    )
    (net (code "70") (name "Net-(Q1B-G)") (class "Default")
      (node (ref "Q1") (pin "4") (pinfunction "G_4") (pintype "passive"))
      (node (ref "R10") (pin "2") (pinfunction "2_2") (pintype "passive"))
      (node (ref "R14") (pin "1") (pinfunction "1_1") (pintype "passive"))
    )
    (net (code "71") (name "Net-(Q2A-G)") (class "Default")
      (node (ref "Q2") (pin "2") (pinfunction "G_2") (pintype "passive"))
      (node (ref "R11") (pin "1") (pinfunction "1_1") (pintype "passive"))
      (node (ref "R13") (pin "2") (pinfunction "2_2") (pintype "passive"))
    )
    (net (code "72") (name "Net-(Q2B-G)") (class "Default")
      (node (ref "Q2") (pin "4") (pinfunction "G_4") (pintype "passive"))
      (node (ref "R20") (pin "2") (pinfunction "2_2") (pintype "passive"))
      (node (ref "R21") (pin "1") (pinfunction "1_1") (pintype "passive"))
    )
    (net (code "73") (name "Net-(Q3A-G)") (class "Default")
      (node (ref "Q3") (pin "2") (pinfunction "G_2") (pintype "passive"))
      (node (ref "R25") (pin "2") (pinfunction "2_2") (pintype "passive"))
      (node (ref "R26") (pin "1") (pinfunction "1_1") (pintype "passive"))
    )
    (net (code "74") (name "Net-(Q3B-G)") (class "Default")
      (node (ref "Q3") (pin "4") (pinfunction "G_4") (pintype "passive"))
      (node (ref "R30") (pin "2") (pinfunction "2_2") (pintype "passive"))
      (node (ref "R31") (pin "1") (pinfunction "1_1") (pintype "passive"))
    )
    (net (code "75") (name "Net-(Q4A-G)") (class "Default")
      (node (ref "Q4") (pin "2") (pinfunction "G_2") (pintype "passive"))
      (node (ref "R35") (pin "2") (pinfunction "2_2") (pintype "passive"))
      (node (ref "R36") (pin "1") (pinfunction "1_1") (pintype "passive"))
    )
    (net (code "76") (name "Net-(Q4B-G)") (class "Default")
      (node (ref "Q4") (pin "4") (pinfunction "G_4") (pintype "passive"))
      (node (ref "R38") (pin "2") (pinfunction "2_2") (pintype "passive"))
      (node (ref "R41") (pin "1") (pinfunction "1_1") (pintype "passive"))
    )
    (net (code "77") (name "Net-(Q5A-G)") (class "Default")
      (node (ref "Q5") (pin "2") (pinfunction "G_2") (pintype "passive"))
      (node (ref "R8") (pin "1") (pinfunction "1_1") (pintype "passive"))
    )
    (net (code "78") (name "Net-(Q5B-G)") (class "Default")
      (node (ref "Q5") (pin "4") (pinfunction "G_4") (pintype "passive"))
      (node (ref "R15") (pin "1") (pinfunction "1_1") (pintype "passive"))
    )
    (net (code "79") (name "Net-(Q6A-G)") (class "Default")
      (node (ref "Q6") (pin "2") (pinfunction "G_2") (pintype "passive"))
      (node (ref "R17") (pin "1") (pinfunction "1_1") (pintype "passive"))
    )
    (net (code "80") (name "Net-(Q6B-G)") (class "Default")
      (node (ref "Q6") (pin "4") (pinfunction "G_4") (pintype "passive"))
      (node (ref "R22") (pin "1") (pinfunction "1_1") (pintype "passive"))
    )
    (net (code "81") (name "Net-(Q7A-G)") (class "Default")
      (node (ref "Q7") (pin "2") (pinfunction "G_2") (pintype "passive"))
      (node (ref "R27") (pin "1") (pinfunction "1_1") (pintype "passive"))
    )
    (net (code "82") (name "Net-(Q7B-G)") (class "Default")
      (node (ref "Q7") (pin "4") (pinfunction "G_4") (pintype "passive"))
      (node (ref "R32") (pin "1") (pinfunction "1_1") (pintype "passive"))
    )
    (net (code "83") (name "Net-(Q8A-G)") (class "Default")
      (node (ref "Q8") (pin "2") (pinfunction "G_2") (pintype "passive"))
      (node (ref "R37") (pin "1") (pinfunction "1_1") (pintype "passive"))
    )
    (net (code "84") (name "Net-(Q8B-G)") (class "Default")
      (node (ref "Q8") (pin "4") (pinfunction "G_4") (pintype "passive"))
      (node (ref "R42") (pin "1") (pinfunction "1_1") (pintype "passive"))
    )
    (net (code "85") (name "Net-(Q9A-D1)") (class "Default")
      (node (ref "Q9") (pin "5") (pinfunction "D1_5") (pintype "passive"))
      (node (ref "Q9") (pin "6") (pinfunction "D2_6") (pintype "passive"))
      (node (ref "Q9") (pin "7") (pinfunction "D2_7") (pintype "passive"))
      (node (ref "Q9") (pin "8") (pinfunction "D1_8") (pintype "passive"))
      (node (ref "X1") (pin "2") (pinfunction "1_2") (pintype "passive"))
    )
    (net (code "86") (name "Net-(Q9A-G)") (class "Default")
      (node (ref "Q9") (pin "2") (pinfunction "G_2") (pintype "passive"))
      (node (ref "Q9") (pin "4") (pinfunction "G_4") (pintype "passive"))
      (node (ref "R18") (pin "2") (pinfunction "2_2") (pintype "passive"))
    )
    (net (code "87") (name "Net-(Q10-PadB)") (class "Default")
      (node (ref "Q10") (pin "B") (pinfunction "B_B") (pintype "passive"))
      (node (ref "R3") (pin "1") (pinfunction "1_1") (pintype "passive"))
    )
    (net (code "88") (name "Net-(R16-Pad2)") (class "Default")
      (node (ref "R16") (pin "2") (pinfunction "2_2") (pintype "passive"))
      (node (ref "R3") (pin "2") (pinfunction "2_2") (pintype "passive"))
      (node (ref "TR10") (pin "C") (pinfunction "C_C") (pintype "passive"))
    )
    (net (code "89") (name "Net-(R28-Pad1)") (class "Default")
      (node (ref "R28") (pin "1") (pinfunction "1_1") (pintype "passive"))
      (node (ref "TR10") (pin "B") (pinfunction "B_B") (pintype "passive"))
    )
    (net (code "90") (name "Net-(R45-Pad1)") (class "Default")
      (node (ref "R45") (pin "1") (pinfunction "1_1") (pintype "passive"))
      (node (ref "TR12") (pin "B") (pinfunction "B_B") (pintype "passive"))
    )
    (net (code "91") (name "Net-(U1-UD+)") (class "Default")
      (node (ref "U$3") (pin "D+") (pinfunction "D+_D+") (pintype "bidirectional"))
      (node (ref "U1") (pin "1") (pinfunction "UD+_1") (pintype "bidirectional"))
    )
    (net (code "92") (name "Net-(U1-UD-)") (class "Default")
      (node (ref "U$3") (pin "D-") (pinfunction "D-_D-") (pintype "bidirectional"))
      (node (ref "U1") (pin "2") (pinfunction "UD-_2") (pintype "bidirectional"))
    )
    (net (code "93") (name "Net-(U1-V3)") (class "Default")
      (node (ref "C1") (pin "1") (pinfunction "1_1") (pintype "passive"))
      (node (ref "U1") (pin "8") (pinfunction "V3_8") (pintype "bidirectional"))
    )
    (net (code "94") (name "Net-(U3-GP2)") (class "Default")
      (node (ref "R28") (pin "2") (pinfunction "2_2") (pintype "passive"))
      (node (ref "U3") (pin "P2") (pinfunction "GP2_P2") (pintype "bidirectional"))
    )
    (net (code "95") (name "Net-(U3-GP3)") (class "Default")
      (node (ref "R46") (pin "2") (pinfunction "2_2") (pintype "passive"))
      (node (ref "TR12") (pin "E") (pinfunction "E_E") (pintype "passive"))
      (node (ref "U3") (pin "P3") (pinfunction "GP3_P3") (pintype "bidirectional"))
    )
    (net (code "96") (name "Net-(U3-GP6)") (class "Default")
      (node (ref "R9") (pin "2") (pinfunction "2_2") (pintype "passive"))
      (node (ref "U3") (pin "P6") (pinfunction "GP6_P6") (pintype "bidirectional"))
      (node (ref "X1") (pin "4") (pinfunction "1_4") (pintype "passive"))
    )
    (net (code "97") (name "Net-(U3-GP7)") (class "Default")
      (node (ref "R18") (pin "1") (pinfunction "1_1") (pintype "passive"))
      (node (ref "U3") (pin "P7") (pinfunction "GP7_P7") (pintype "bidirectional"))
    )
    (net (code "98") (name "Net-(U3-GP13)") (class "Default")
      (node (ref "U3") (pin "P13") (pinfunction "GP13_P13") (pintype "bidirectional"))
      (node (ref "X2") (pin "1") (pinfunction "S_1") (pintype "passive"))
    )
    (net (code "99") (name "Net-(U3-GP14)") (class "Default")
      (node (ref "U3") (pin "P14") (pinfunction "GP14_P14") (pintype "bidirectional"))
      (node (ref "X2") (pin "2") (pinfunction "S_2") (pintype "passive"))
    )
    (net (code "100") (name "Net-(U3-GP15)") (class "Default")
      (node (ref "U3") (pin "P15") (pinfunction "GP15_P15") (pintype "bidirectional"))
      (node (ref "X2") (pin "3") (pinfunction "S_3") (pintype "passive"))
    )
    (net (code "101") (name "Net-(U3-GP26)") (class "Default")
      (node (ref "U3") (pin "P26") (pinfunction "GP26_P26") (pintype "bidirectional"))
      (node (ref "X2") (pin "4") (pinfunction "S_4") (pintype "passive"))
    )
    (net (code "102") (name "Net-(U3-GP27)") (class "Default")
      (node (ref "U3") (pin "P27") (pinfunction "GP27_P27") (pintype "bidirectional"))
      (node (ref "X2") (pin "5") (pinfunction "S_5") (pintype "passive"))
    )
    (net (code "103") (name "Net-(U3-GP28)") (class "Default")
      (node (ref "U3") (pin "P28") (pinfunction "GP28_P28") (pintype "bidirectional"))
      (node (ref "X2") (pin "6") (pinfunction "S_6") (pintype "passive"))
    )
    (net (code "104") (name "Net-(X1F-1)") (class "Default")
      (node (ref "Q10") (pin "E") (pinfunction "E_E") (pintype "passive"))
      (node (ref "X1") (pin "6") (pinfunction "1_6") (pintype "passive"))
    )
    (net (code "105") (name "Net-(X1G-1)") (class "Default")
      (node (ref "R45") (pin "2") (pinfunction "2_2") (pintype "passive"))
      (node (ref "X1") (pin "7") (pinfunction "1_7") (pintype "passive"))
    )
    (net (code "106") (name "Net-(X3A-S)") (class "Default")
      (node (ref "R49") (pin "2") (pinfunction "2_2") (pintype "passive"))
      (node (ref "X3") (pin "1") (pinfunction "S_1") (pintype "passive"))
    )
    (net (code "107") (name "Net-(X3B-S)") (class "Default")
      (node (ref "R48") (pin "2") (pinfunction "2_2") (pintype "passive"))
      (node (ref "X3") (pin "2") (pinfunction "S_2") (pintype "passive"))
    )
    (net (code "108") (name "Net-(X3C-S)") (class "Default")
      (node (ref "R47") (pin "2") (pinfunction "2_2") (pintype "passive"))
      (node (ref "X3") (pin "3") (pinfunction "S_3") (pintype "passive"))
    )
    (net (code "109") (name "Net-(X3D-S)") (class "Default")
      (node (ref "R44") (pin "2") (pinfunction "2_2") (pintype "passive"))
      (node (ref "X3") (pin "4") (pinfunction "S_4") (pintype "passive"))
    )
    (net (code "110") (name "Net-(X3E-S)") (class "Default")
      (node (ref "R43") (pin "2") (pinfunction "2_2") (pintype "passive"))
      (node (ref "X3") (pin "5") (pinfunction "S_5") (pintype "passive"))
    )
    (net (code "111") (name "Net-(X3F-S)") (class "Default")
      (node (ref "R39") (pin "2") (pinfunction "2_2") (pintype "passive"))
      (node (ref "X3") (pin "6") (pinfunction "S_6") (pintype "passive"))
    )
    (net (code "112") (name "Net-(X6B-S)") (class "Default")
      (node (ref "D1") (pin "A") (pinfunction "A_A") (pintype "passive"))
      (node (ref "J3") (pin "3") (pinfunction "3_3") (pintype "passive"))
      (node (ref "X6") (pin "2") (pinfunction "S_2") (pintype "passive"))
    )
    (net (code "113") (name "OFFSET_INT") (class "Default")
      (node (ref "D3") (pin "C") (pinfunction "C_C") (pintype "passive"))
      (node (ref "D4") (pin "C") (pinfunction "C_C") (pintype "passive"))
      (node (ref "D6") (pin "C") (pinfunction "C_C") (pintype "passive"))
      (node (ref "U3") (pin "P12") (pinfunction "GP12_P12") (pintype "bidirectional"))
    )
    (net (code "114") (name "SH_CP") (class "Default")
      (node (ref "IC1") (pin "11") (pinfunction "SH_CK_11") (pintype "input"))
      (node (ref "IC2") (pin "11") (pinfunction "SH_CK_11") (pintype "input"))
      (node (ref "U3") (pin "P10") (pinfunction "GP10_P10") (pintype "bidirectional"))
    )
    (net (code "115") (name "ST_CP") (class "Default")
      (node (ref "IC1") (pin "12") (pinfunction "ST_CK_12") (pintype "input"))
      (node (ref "IC2") (pin "12") (pinfunction "ST_CK_12") (pintype "input"))
      (node (ref "U3") (pin "P9") (pinfunction "GP9_P9") (pintype "bidirectional"))
    )
    (net (code "116") (name "VCC") (class "Default")
      (node (ref "C3") (pin "+") (pinfunction "+_+") (pintype "passive"))
      (node (ref "IC4") (pin "1") (pinfunction "IN_1") (pintype "input"))
      (node (ref "Q10") (pin "C") (pinfunction "C_C") (pintype "passive"))
      (node (ref "R16") (pin "1") (pinfunction "1_1") (pintype "passive"))
      (node (ref "R24") (pin "1") (pinfunction "1_1") (pintype "passive"))
    )
    (net (code "117") (name "unconnected-(IC1A-Q7'-Pad9)") (class "Default")
      (node (ref "IC1") (pin "9") (pinfunction "Q7'_9") (pintype "tri_state"))
    )
    (net (code "118") (name "unconnected-(IC3-CD+-Pad10)") (class "Default")
      (node (ref "IC3") (pin "10") (pinfunction "CD+_10") (pintype "passive"))
    )
    (net (code "119") (name "unconnected-(IC5-CD+-Pad10)") (class "Default")
      (node (ref "IC5") (pin "10") (pinfunction "CD+_10") (pintype "passive"))
    )
    (net (code "120") (name "unconnected-(IC5-I1-Pad1)") (class "Default")
      (node (ref "IC5") (pin "1") (pinfunction "I1_1") (pintype "input"))
    )
    (net (code "121") (name "unconnected-(IC5-I2-Pad2)") (class "Default")
      (node (ref "IC5") (pin "2") (pinfunction "I2_2") (pintype "input"))
    )
    (net (code "122") (name "unconnected-(IC5-O1-Pad18)") (class "Default")
      (node (ref "IC5") (pin "18") (pinfunction "O1_18") (pintype "open_collector"))
    )
    (net (code "123") (name "unconnected-(IC5-O2-Pad17)") (class "Default")
      (node (ref "IC5") (pin "17") (pinfunction "O2_17") (pintype "open_collector"))
    )
    (net (code "124") (name "unconnected-(J3-Pad2)") (class "Default")
      (node (ref "J3") (pin "2") (pinfunction "2_2") (pintype "passive"))
    )
    (net (code "125") (name "unconnected-(RN1-Pad1)") (class "Default")
      (node (ref "RN1") (pin "1") (pinfunction "1_1") (pintype "passive"))
    )
    (net (code "126") (name "unconnected-(RN1B-1-Pad2)") (class "Default")
      (node (ref "RN1") (pin "2") (pinfunction "1_2") (pintype "passive"))
    )
    (net (code "127") (name "unconnected-(RN2-Pad1)") (class "Default")
      (node (ref "RN2") (pin "1") (pinfunction "1_1") (pintype "passive"))
    )
    (net (code "128") (name "unconnected-(RN2B-1-Pad2)") (class "Default")
      (node (ref "RN2") (pin "2") (pinfunction "1_2") (pintype "passive"))
    )
    (net (code "129") (name "unconnected-(U$3-VBUS-PadV)") (class "Default")
      (node (ref "U$3") (pin "V") (pinfunction "VBUS_V") (pintype "bidirectional"))
    )
    (net (code "130") (name "unconnected-(U1-RTS#-Pad4)") (class "Default")
      (node (ref "U1") (pin "4") (pinfunction "RTS#_4") (pintype "bidirectional"))
    )
    (net (code "131") (name "unconnected-(U3-GP17-PadP17)") (class "Default")
      (node (ref "U3") (pin "P17") (pinfunction "GP17_P17") (pintype "bidirectional"))
    )
    (net (code "132") (name "unconnected-(U3-GP18-PadP18)") (class "Default")
      (node (ref "U3") (pin "P18") (pinfunction "GP18_P18") (pintype "bidirectional"))
    )
    (net (code "133") (name "unconnected-(U3-GP19-PadP19)") (class "Default")
      (node (ref "U3") (pin "P19") (pinfunction "GP19_P19") (pintype "bidirectional"))
    )
    (net (code "134") (name "unconnected-(U3-GP20-PadP20)") (class "Default")
      (node (ref "U3") (pin "P20") (pinfunction "GP20_P20") (pintype "bidirectional"))
    )
    (net (code "135") (name "unconnected-(U3-GP21-PadP21)") (class "Default")
      (node (ref "U3") (pin "P21") (pinfunction "GP21_P21") (pintype "bidirectional"))
    )
    (net (code "136") (name "unconnected-(U3-GP22-PadP22)") (class "Default")
      (node (ref "U3") (pin "P22") (pinfunction "GP22_P22") (pintype "bidirectional"))
    )
    (net (code "137") (name "unconnected-(U3-GP23-PadP23)") (class "Default")
      (node (ref "U3") (pin "P23") (pinfunction "GP23_P23") (pintype "bidirectional"))
    )
    (net (code "138") (name "unconnected-(U3-GP24-PadP24)") (class "Default")
      (node (ref "U3") (pin "P24") (pinfunction "GP24_P24") (pintype "bidirectional"))
    )
    (net (code "139") (name "unconnected-(U3-GP25-PadP25)") (class "Default")
      (node (ref "U3") (pin "P25") (pinfunction "GP25_P25") (pintype "bidirectional"))
    )
    (net (code "140") (name "unconnected-(U3-GP29-PadP29)") (class "Default")
      (node (ref "U3") (pin "P29") (pinfunction "GP29_P29") (pintype "bidirectional"))
    )
  )
)
